# W5500_Module.net
KiCad netlist of a schematic drawn in Altium Designer
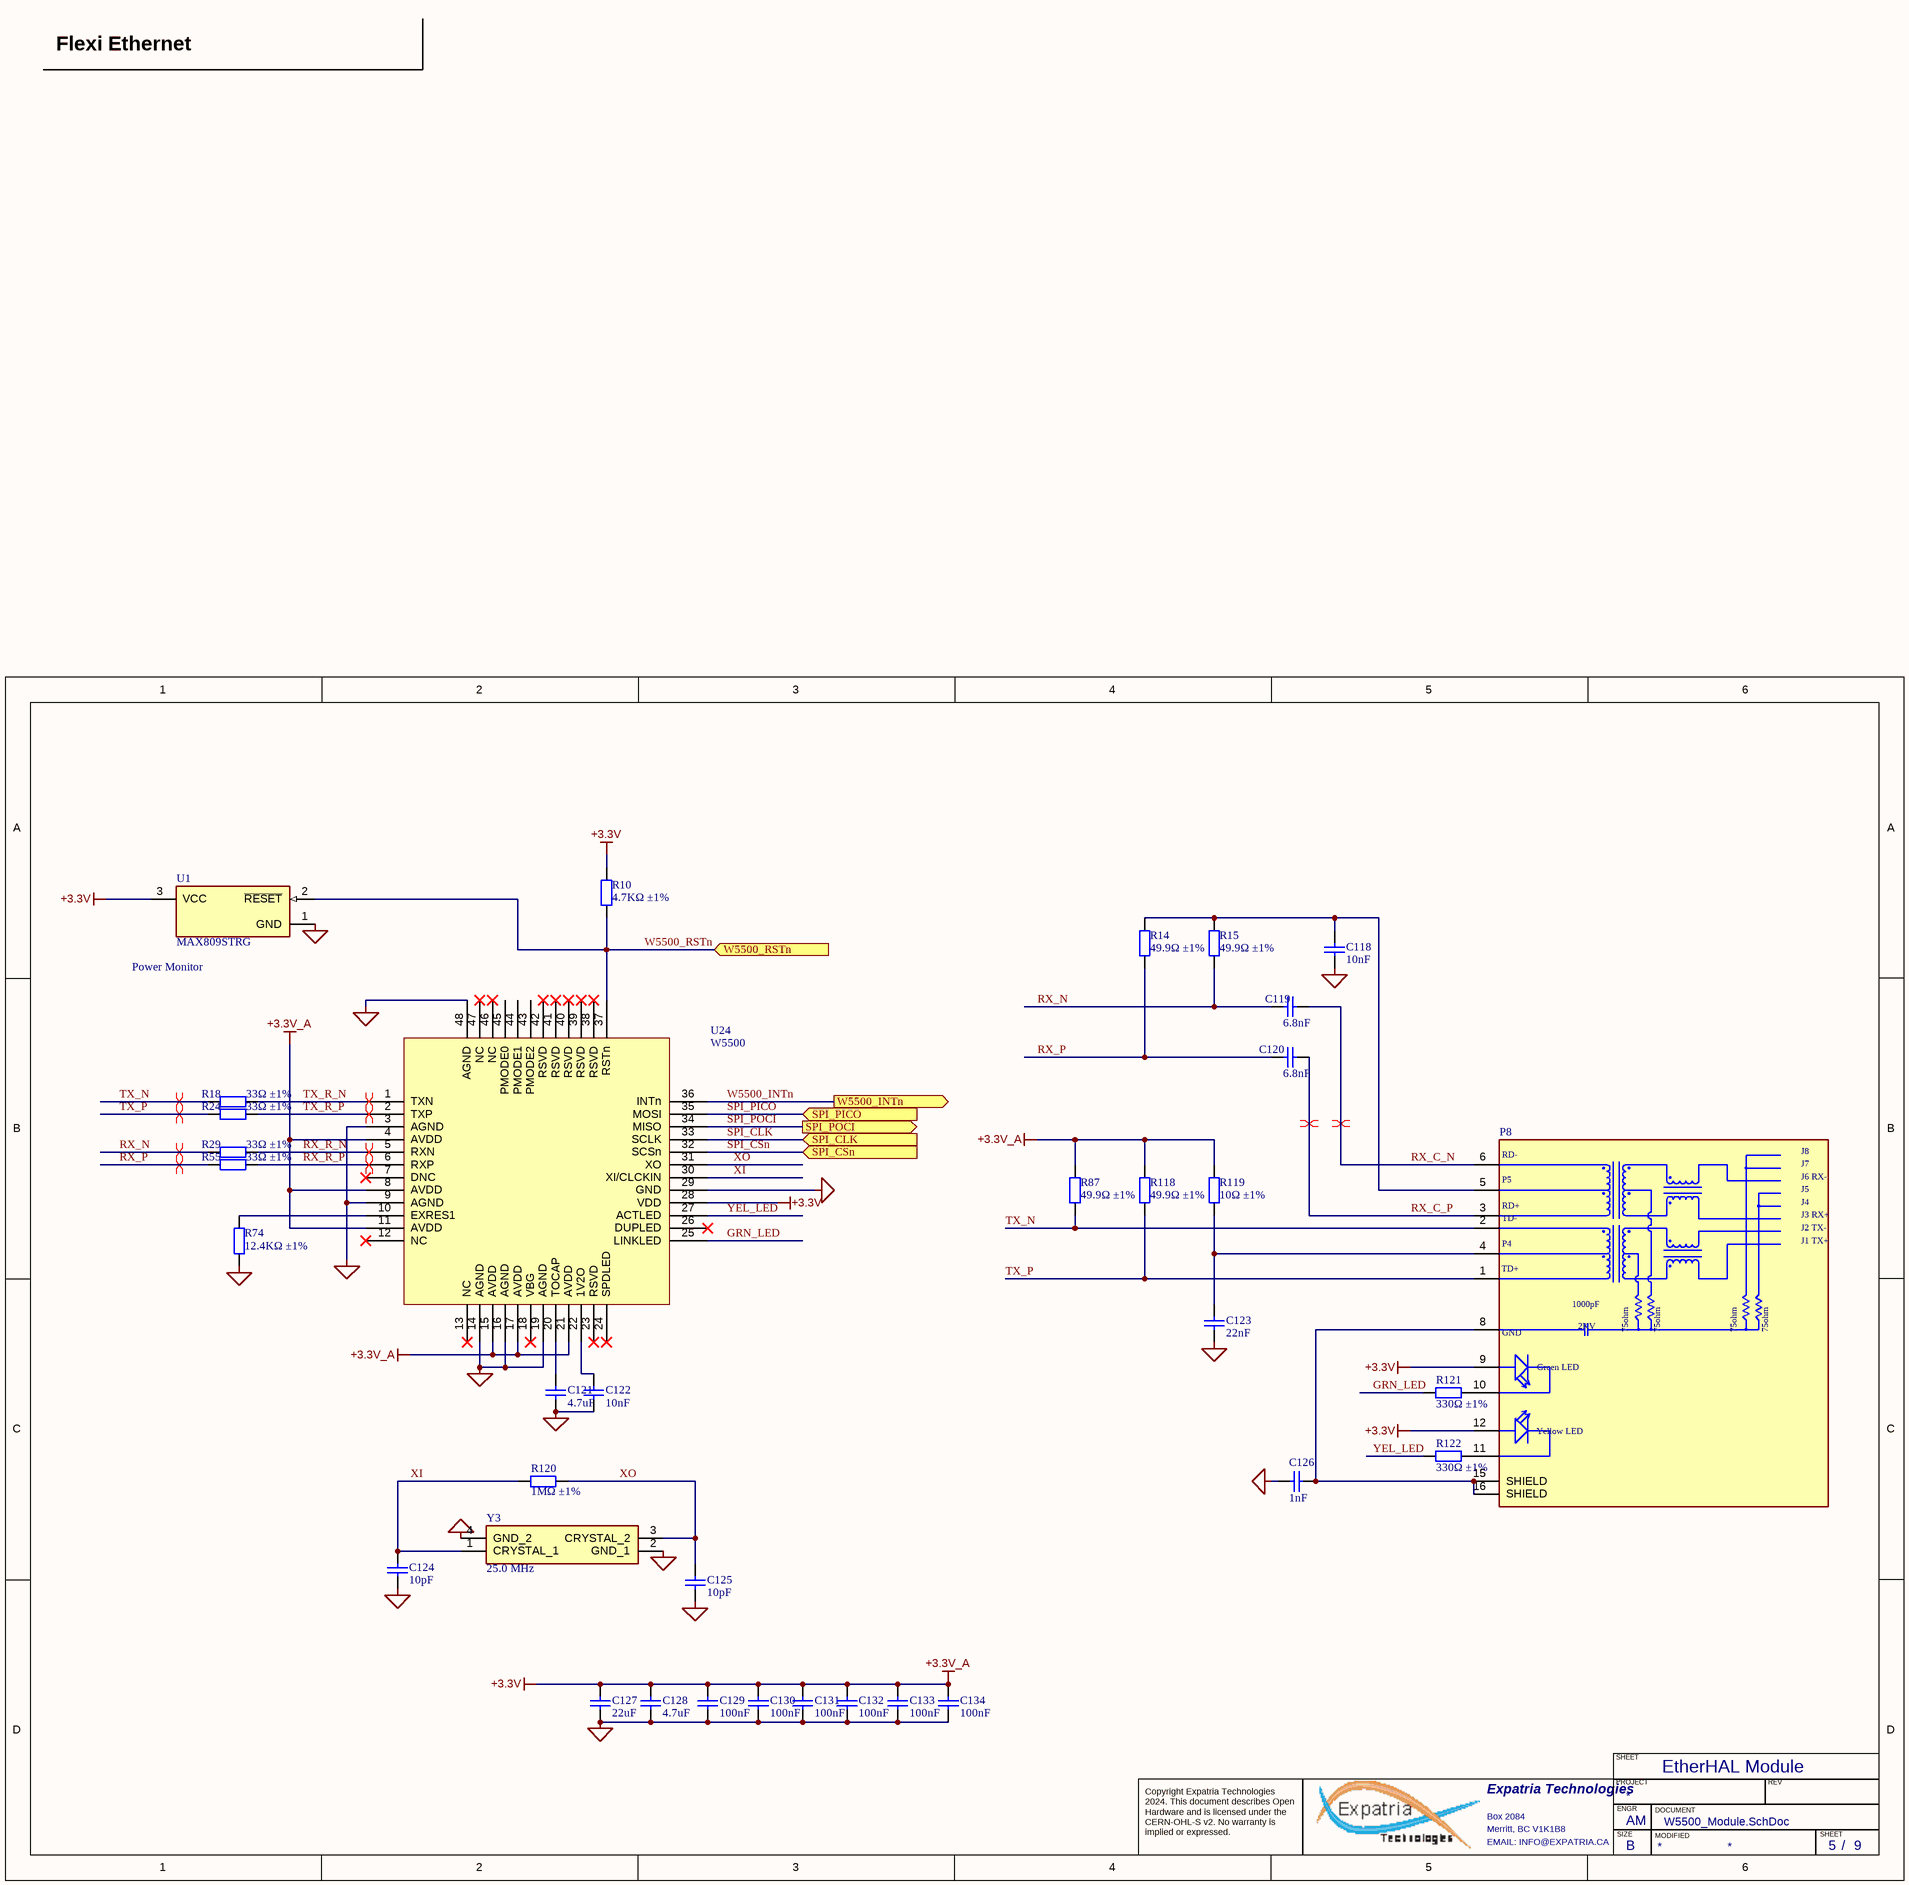
[diagram p0: W5500_Module.SchDoc]

(export (version "E")
  (design (tool "Eeschema 10.0.6"))
  (components
    (comp (ref "C118")
      (value "10nF")
      (footprint "0402_C")
      (description "Chip capacitors")
      (fields
        (field (name "MANUFACTURER") "Samsung Electro-Mechanics")
        (field (name "PARTNUMBER") "CL05B103KB5NNNC")
      )
      (libsource (lib "Cap") (part "0402 10nF (103) 10% 50V"))
    )
    (comp (ref "C119")
      (value "6.8nF")
      (footprint "0402_C")
      (description "Chip capacitors")
      (fields
        (field (name "MANUFACTURER") "Guangdong Fenghua Advanced Tech")
        (field (name "PARTNUMBER") "0402B682K500NT")
      )
      (libsource (lib "Cap") (part "0402 6.8nF (682) 10% 50V"))
    )
    (comp (ref "C120")
      (value "6.8nF")
      (footprint "0402_C")
      (description "Chip capacitors")
      (fields
        (field (name "MANUFACTURER") "Guangdong Fenghua Advanced Tech")
        (field (name "PARTNUMBER") "0402B682K500NT")
      )
      (libsource (lib "Cap") (part "0402 6.8nF (682) 10% 50V"))
    )
    (comp (ref "C121")
      (value "4.7uF")
      (footprint "0402_C")
      (description "Chip capacitor")
      (fields
        (field (name "MANUFACTURER") "Samsung Electro-Mechanics")
        (field (name "PARTNUMBER") "CL05A475MP5NRNC")
      )
      (libsource (lib "Cap") (part "0402 4.7uF (475) 20% 10V"))
    )
    (comp (ref "C122")
      (value "10nF")
      (footprint "0402_C")
      (description "Chip capacitors")
      (fields
        (field (name "MANUFACTURER") "Samsung Electro-Mechanics")
        (field (name "PARTNUMBER") "CL05B103KB5NNNC")
      )
      (libsource (lib "Cap") (part "0402 10nF (103) 10% 50V"))
    )
    (comp (ref "C123")
      (value "22nF")
      (footprint "0402_C")
      (description "Chip capacitors")
      (fields
        (field (name "MANUFACTURER") "Guangdong Fenghua Advanced Tech")
        (field (name "PARTNUMBER") "0402B223K500NT")
      )
      (libsource (lib "Cap") (part "0402 22nF (223) 10% 50V"))
    )
    (comp (ref "C124")
      (value "10pF")
      (footprint "0402_C")
      (description "Chip capacitors")
      (fields
        (field (name "MANUFACTURER") "Samsung Electro-Mechanics")
        (field (name "PARTNUMBER") "CL05C100JB5NNNC")
      )
      (libsource (lib "Cap") (part "0402 10pF (100) 5% 50V"))
    )
    (comp (ref "C125")
      (value "10pF")
      (footprint "0402_C")
      (description "Chip capacitors")
      (fields
        (field (name "MANUFACTURER") "Samsung Electro-Mechanics")
        (field (name "PARTNUMBER") "CL05C100JB5NNNC")
      )
      (libsource (lib "Cap") (part "0402 10pF (100) 5% 50V"))
    )
    (comp (ref "C126")
      (value "1nF")
      (footprint "1206_C")
      (description "Chip capacitors")
      (fields
        (field (name "MANUFACTURER") "Samsung Electro-Mechanics")
        (field (name "PARTNUMBER") "CL31B102KGFNNNE")
      )
      (libsource (lib "Cap") (part "1206 1nF (102) 10% 500V"))
    )
    (comp (ref "C127")
      (value "22uF")
      (footprint "0805_C")
      (description "Chip capacitors")
      (fields
        (field (name "MANUFACTURER") "Samsung Electro-Mechanics")
        (field (name "PARTNUMBER") "CL21A226MAQNNNE")
      )
      (libsource (lib "Cap") (part "0805 22uF (226) 20% 25V"))
    )
    (comp (ref "C128")
      (value "4.7uF")
      (footprint "0603_C")
      (description "Chip capacitors")
      (fields
        (field (name "MANUFACTURER") "Samsung Electro-Mechanics")
        (field (name "PARTNUMBER") "CL10A475KO8NNNC")
      )
      (libsource (lib "Cap") (part "0603 4.7uF (475) 10% 16V"))
    )
    (comp (ref "C129")
      (value "100nF")
      (footprint "0402_C")
      (description "Chip capacitors")
      (fields
        (field (name "MANUFACTURER") "Samsung Electro-Mechanics")
        (field (name "PARTNUMBER") "CL05B104KO5NNNC")
      )
      (libsource (lib "Cap") (part "0402 100nF (104) 10% 16V"))
    )
    (comp (ref "C130")
      (value "100nF")
      (footprint "0402_C")
      (description "Chip capacitors")
      (fields
        (field (name "MANUFACTURER") "Samsung Electro-Mechanics")
        (field (name "PARTNUMBER") "CL05B104KO5NNNC")
      )
      (libsource (lib "Cap") (part "0402 100nF (104) 10% 16V"))
    )
    (comp (ref "C131")
      (value "100nF")
      (footprint "0402_C")
      (description "Chip capacitors")
      (fields
        (field (name "MANUFACTURER") "Samsung Electro-Mechanics")
        (field (name "PARTNUMBER") "CL05B104KO5NNNC")
      )
      (libsource (lib "Cap") (part "0402 100nF (104) 10% 16V"))
    )
    (comp (ref "C132")
      (value "100nF")
      (footprint "0402_C")
      (description "Chip capacitors")
      (fields
        (field (name "MANUFACTURER") "Samsung Electro-Mechanics")
        (field (name "PARTNUMBER") "CL05B104KO5NNNC")
      )
      (libsource (lib "Cap") (part "0402 100nF (104) 10% 16V"))
    )
    (comp (ref "C133")
      (value "100nF")
      (footprint "0402_C")
      (description "Chip capacitors")
      (fields
        (field (name "MANUFACTURER") "Samsung Electro-Mechanics")
        (field (name "PARTNUMBER") "CL05B104KO5NNNC")
      )
      (libsource (lib "Cap") (part "0402 100nF (104) 10% 16V"))
    )
    (comp (ref "C134")
      (value "100nF")
      (footprint "0402_C")
      (description "Chip capacitors")
      (fields
        (field (name "MANUFACTURER") "Samsung Electro-Mechanics")
        (field (name "PARTNUMBER") "CL05B104KO5NNNC")
      )
      (libsource (lib "Cap") (part "0402 100nF (104) 10% 16V"))
    )
    (comp (ref "P8")
      (value "~")
      (footprint "HANRUN_HR911105A")
      (description "HR911105A Ethernet Interface Arduino Platform Evaluation Expansion Board")
      (fields (field (name "MP") "HR911105A") (field (name "MF") "DFRobot"))
      (libsource (lib "Universal_CNC_Breakout") (part "HR911105A"))
    )
    (comp (ref "R10")
      (value "4.7KΩ ±1%")
      (footprint "0402_R")
      (description "Chip resistor")
      (fields (field (name "MANUFACTURER") "Uniroyal Elec") (field (name "PARTNUMBER") "0402WGF4701TCE"))
      (libsource (lib "RES") (part "0402 4.7K (4701) 1%"))
    )
    (comp (ref "R14")
      (value "49.9Ω ±1%")
      (footprint "0402_R")
      (description "Chip resistor")
      (fields (field (name "MANUFACTURER") "Uniroyal Elec") (field (name "PARTNUMBER") "0402WGF499JTCE"))
      (libsource (lib "RES") (part "0402 49.9R (49R9) 1%"))
    )
    (comp (ref "R15")
      (value "49.9Ω ±1%")
      (footprint "0402_R")
      (description "Chip resistor")
      (fields (field (name "MANUFACTURER") "Uniroyal Elec") (field (name "PARTNUMBER") "0402WGF499JTCE"))
      (libsource (lib "RES") (part "0402 49.9R (49R9) 1%"))
    )
    (comp (ref "R18")
      (value "33Ω ±1%")
      (footprint "0402_R")
      (description "Chip resistor")
      (fields (field (name "MANUFACTURER") "Uniroyal Elec") (field (name "PARTNUMBER") "0402WGF330JTCE"))
      (libsource (lib "RES") (part "0402 33R (33R0) 1%"))
    )
    (comp (ref "R24")
      (value "33Ω ±1%")
      (footprint "0402_R")
      (description "Chip resistor")
      (fields (field (name "MANUFACTURER") "Uniroyal Elec") (field (name "PARTNUMBER") "0402WGF330JTCE"))
      (libsource (lib "RES") (part "0402 33R (33R0) 1%"))
    )
    (comp (ref "R29")
      (value "33Ω ±1%")
      (footprint "0402_R")
      (description "Chip resistor")
      (fields (field (name "MANUFACTURER") "Uniroyal Elec") (field (name "PARTNUMBER") "0402WGF330JTCE"))
      (libsource (lib "RES") (part "0402 33R (33R0) 1%"))
    )
    (comp (ref "R55")
      (value "33Ω ±1%")
      (footprint "0402_R")
      (description "Chip resistor")
      (fields (field (name "MANUFACTURER") "Uniroyal Elec") (field (name "PARTNUMBER") "0402WGF330JTCE"))
      (libsource (lib "RES") (part "0402 33R (33R0) 1%"))
    )
    (comp (ref "R74")
      (value "12.4KΩ ±1%")
      (footprint "0603_R")
      (description "Chip resistor")
      (fields (field (name "MANUFACTURER") "Uniroyal Elec") (field (name "PARTNUMBER") "0603WAF1242T5E"))
      (libsource (lib "RES") (part "0603 10K (1002) 1%"))
    )
    (comp (ref "R87")
      (value "49.9Ω ±1%")
      (footprint "0402_R")
      (description "Chip resistor")
      (fields (field (name "MANUFACTURER") "Uniroyal Elec") (field (name "PARTNUMBER") "0402WGF499JTCE"))
      (libsource (lib "RES") (part "0402 49.9R (49R9) 1%"))
    )
    (comp (ref "R118")
      (value "49.9Ω ±1%")
      (footprint "0402_R")
      (description "Chip resistor")
      (fields (field (name "MANUFACTURER") "Uniroyal Elec") (field (name "PARTNUMBER") "0402WGF499JTCE"))
      (libsource (lib "RES") (part "0402 49.9R (49R9) 1%"))
    )
    (comp (ref "R119")
      (value "10Ω ±1%")
      (footprint "0402_R")
      (description "Chip resistor")
      (fields (field (name "MANUFACTURER") "Uniroyal Elec") (field (name "PARTNUMBER") "0402WGF100JTCE"))
      (libsource (lib "RES") (part "0402 10R (10R0) 1%"))
    )
    (comp (ref "R120")
      (value "1MΩ ±1%")
      (footprint "0402_R")
      (description "Chip resistor")
      (fields (field (name "MANUFACTURER") "Uniroyal Elec") (field (name "PARTNUMBER") "0402WGF1004TCE"))
      (libsource (lib "RES") (part "0402 1M (1004) 1%"))
    )
    (comp (ref "R121")
      (value "330Ω ±1%")
      (footprint "0402_R")
      (description "Chip resistor")
      (fields (field (name "MANUFACTURER") "Uniroyal Elec") (field (name "PARTNUMBER") "0402WGF3300TCE"))
      (libsource (lib "RES") (part "0402 330R (3300) 1%"))
    )
    (comp (ref "R122")
      (value "330Ω ±1%")
      (footprint "0402_R")
      (description "Chip resistor")
      (fields (field (name "MANUFACTURER") "Uniroyal Elec") (field (name "PARTNUMBER") "0402WGF3300TCE"))
      (libsource (lib "RES") (part "0402 330R (3300) 1%"))
    )
    (comp (ref "U1")
      (value "MAX809STRG")
      (footprint "FP-318-08-MFG")
      (description "IC MPU SUPERVISORY 2.93V SOT23")
      (fields
        (field (name "OCTOPART") "https://octopart.com/max809strg-on+semiconductor-509853")
        (field (name "MANUFACTURER") "ON SEMICONDUCTOR")
      )
      (libsource (lib "Altium Content Vault") (part "10e2fe7115e7b167e7ed62dcbcd754e"))
    )
    (comp (ref "U24")
      (value "W5500")
      (footprint "LQFP-48_7x7x05P")
      (description "Ethernet Controllers 2.97V ~ 3.63V 10/100 Base-T/TX PHY SPI LQFP-48_7x7x05P Ethernet ICs ROHS")
      (libsource (lib "IC") (part "W5500_[C32843]"))
    )
    (comp (ref "Y3")
      (value "25.0 MHz")
      (footprint "YSX321SL")
      (description "Crystal or Oscillator")
      (fields (field (name "MANUFACTURER_PART_NUMBER") "X322525MSB4SI"))
      (libsource (lib "*") (part "YSX321SL"))
    )
  )
  (nets
    (net (code "1") (name "+3.3V") (class "Default")
      (node (ref "C127") (pin "2") (pinfunction "2_2") (pintype "passive"))
      (node (ref "C128") (pin "2") (pinfunction "2_2") (pintype "passive"))
      (node (ref "C129") (pin "2") (pinfunction "2_2") (pintype "passive"))
      (node (ref "C130") (pin "2") (pinfunction "2_2") (pintype "passive"))
      (node (ref "C131") (pin "2") (pinfunction "2_2") (pintype "passive"))
      (node (ref "C132") (pin "2") (pinfunction "2_2") (pintype "passive"))
      (node (ref "C133") (pin "2") (pinfunction "2_2") (pintype "passive"))
      (node (ref "C134") (pin "2") (pinfunction "2_2") (pintype "passive"))
      (node (ref "P8") (pin "12") (pinfunction "YA_12") (pintype "passive"))
      (node (ref "P8") (pin "9") (pinfunction "GA_9") (pintype "passive"))
      (node (ref "R10") (pin "1") (pinfunction "1_1") (pintype "passive"))
      (node (ref "R118") (pin "1") (pinfunction "1_1") (pintype "passive"))
      (node (ref "R119") (pin "1") (pinfunction "1_1") (pintype "passive"))
      (node (ref "R87") (pin "1") (pinfunction "1_1") (pintype "passive"))
      (node (ref "U1") (pin "3") (pinfunction "VCC_3") (pintype "power_in"))
      (node (ref "U24") (pin "11") (pinfunction "AVDD_11") (pintype "passive"))
      (node (ref "U24") (pin "15") (pinfunction "AVDD_15") (pintype "passive"))
      (node (ref "U24") (pin "17") (pinfunction "AVDD_17") (pintype "passive"))
      (node (ref "U24") (pin "21") (pinfunction "AVDD_21") (pintype "passive"))
      (node (ref "U24") (pin "28") (pinfunction "VDD_28") (pintype "passive"))
      (node (ref "U24") (pin "4") (pinfunction "AVDD_4") (pintype "passive"))
      (node (ref "U24") (pin "8") (pinfunction "AVDD_8") (pintype "passive"))
    )
    (net (code "2") (name "/GRN_LED") (class "Default")
      (node (ref "R121") (pin "1") (pinfunction "1_1") (pintype "passive"))
      (node (ref "U24") (pin "25") (pinfunction "LINKLED_25") (pintype "passive"))
    )
    (net (code "3") (name "/RX_C_N") (class "Default")
      (node (ref "C119") (pin "1") (pinfunction "1_1") (pintype "passive"))
      (node (ref "P8") (pin "6") (pinfunction "RD-_6") (pintype "passive"))
    )
    (net (code "4") (name "/RX_C_P") (class "Default")
      (node (ref "C120") (pin "1") (pinfunction "1_1") (pintype "passive"))
      (node (ref "P8") (pin "3") (pinfunction "RD+_3") (pintype "passive"))
    )
    (net (code "5") (name "/RX_N") (class "Default")
      (node (ref "C119") (pin "2") (pinfunction "2_2") (pintype "passive"))
      (node (ref "R15") (pin "2") (pinfunction "2_2") (pintype "passive"))
      (node (ref "R29") (pin "1") (pinfunction "1_1") (pintype "passive"))
    )
    (net (code "6") (name "/RX_P") (class "Default")
      (node (ref "C120") (pin "2") (pinfunction "2_2") (pintype "passive"))
      (node (ref "R14") (pin "2") (pinfunction "2_2") (pintype "passive"))
      (node (ref "R55") (pin "1") (pinfunction "1_1") (pintype "passive"))
    )
    (net (code "7") (name "/RX_R_N") (class "Default")
      (node (ref "R29") (pin "2") (pinfunction "2_2") (pintype "passive"))
      (node (ref "U24") (pin "5") (pinfunction "RXN_5") (pintype "passive"))
    )
    (net (code "8") (name "/RX_R_P") (class "Default")
      (node (ref "R55") (pin "2") (pinfunction "2_2") (pintype "passive"))
      (node (ref "U24") (pin "6") (pinfunction "RXP_6") (pintype "passive"))
    )
    (net (code "9") (name "/SPI_CLK") (class "Default")
      (node (ref "U24") (pin "33") (pinfunction "SCLK_33") (pintype "passive"))
    )
    (net (code "10") (name "/SPI_CSn") (class "Default")
      (node (ref "U24") (pin "32") (pinfunction "SCSn_32") (pintype "passive"))
    )
    (net (code "11") (name "/SPI_PICO") (class "Default")
      (node (ref "U24") (pin "35") (pinfunction "MOSI_35") (pintype "passive"))
    )
    (net (code "12") (name "/SPI_POCI") (class "Default")
      (node (ref "U24") (pin "34") (pinfunction "MISO_34") (pintype "passive"))
    )
    (net (code "13") (name "/TX_N") (class "Default")
      (node (ref "P8") (pin "2") (pinfunction "TD-_2") (pintype "passive"))
      (node (ref "R18") (pin "1") (pinfunction "1_1") (pintype "passive"))
      (node (ref "R87") (pin "2") (pinfunction "2_2") (pintype "passive"))
    )
    (net (code "14") (name "/TX_P") (class "Default")
      (node (ref "P8") (pin "1") (pinfunction "TD+_1") (pintype "passive"))
      (node (ref "R118") (pin "2") (pinfunction "2_2") (pintype "passive"))
      (node (ref "R24") (pin "1") (pinfunction "1_1") (pintype "passive"))
    )
    (net (code "15") (name "/TX_R_N") (class "Default")
      (node (ref "R18") (pin "2") (pinfunction "2_2") (pintype "passive"))
      (node (ref "U24") (pin "1") (pinfunction "TXN_1") (pintype "passive"))
    )
    (net (code "16") (name "/TX_R_P") (class "Default")
      (node (ref "R24") (pin "2") (pinfunction "2_2") (pintype "passive"))
      (node (ref "U24") (pin "2") (pinfunction "TXP_2") (pintype "passive"))
    )
    (net (code "17") (name "/W5500_INTn") (class "Default")
      (node (ref "U24") (pin "36") (pinfunction "INTn_36") (pintype "passive"))
    )
    (net (code "18") (name "/W5500_RSTn") (class "Default")
      (node (ref "R10") (pin "2") (pinfunction "2_2") (pintype "passive"))
      (node (ref "U1") (pin "2") (pinfunction "~{RESET}_2") (pintype "input"))
      (node (ref "U24") (pin "37") (pinfunction "RSTn_37") (pintype "passive"))
    )
    (net (code "19") (name "/XI") (class "Default")
      (node (ref "C124") (pin "2") (pinfunction "2_2") (pintype "passive"))
      (node (ref "R120") (pin "1") (pinfunction "1_1") (pintype "passive"))
      (node (ref "U24") (pin "30") (pinfunction "XI/CLCKIN_30") (pintype "passive"))
      (node (ref "Y3") (pin "1") (pinfunction "CRYSTAL_1_1") (pintype "passive"))
    )
    (net (code "20") (name "/XO") (class "Default")
      (node (ref "C125") (pin "2") (pinfunction "2_2") (pintype "passive"))
      (node (ref "R120") (pin "2") (pinfunction "2_2") (pintype "passive"))
      (node (ref "U24") (pin "31") (pinfunction "XO_31") (pintype "passive"))
      (node (ref "Y3") (pin "3") (pinfunction "CRYSTAL_2_3") (pintype "passive"))
    )
    (net (code "21") (name "/YEL_LED") (class "Default")
      (node (ref "R122") (pin "1") (pinfunction "1_1") (pintype "passive"))
      (node (ref "U24") (pin "27") (pinfunction "ACTLED_27") (pintype "passive"))
    )
    (net (code "22") (name "MCU_GND") (class "Default")
      (node (ref "C118") (pin "1") (pinfunction "1_1") (pintype "passive"))
      (node (ref "C121") (pin "1") (pinfunction "1_1") (pintype "passive"))
      (node (ref "C122") (pin "1") (pinfunction "1_1") (pintype "passive"))
      (node (ref "C123") (pin "1") (pinfunction "1_1") (pintype "passive"))
      (node (ref "C124") (pin "1") (pinfunction "1_1") (pintype "passive"))
      (node (ref "C125") (pin "1") (pinfunction "1_1") (pintype "passive"))
      (node (ref "C126") (pin "1") (pinfunction "1_1") (pintype "passive"))
      (node (ref "C127") (pin "1") (pinfunction "1_1") (pintype "passive"))
      (node (ref "C128") (pin "1") (pinfunction "1_1") (pintype "passive"))
      (node (ref "C129") (pin "1") (pinfunction "1_1") (pintype "passive"))
      (node (ref "C130") (pin "1") (pinfunction "1_1") (pintype "passive"))
      (node (ref "C131") (pin "1") (pinfunction "1_1") (pintype "passive"))
      (node (ref "C132") (pin "1") (pinfunction "1_1") (pintype "passive"))
      (node (ref "C133") (pin "1") (pinfunction "1_1") (pintype "passive"))
      (node (ref "C134") (pin "1") (pinfunction "1_1") (pintype "passive"))
      (node (ref "R74") (pin "1") (pinfunction "1_1") (pintype "passive"))
      (node (ref "U1") (pin "1") (pinfunction "GND_1") (pintype "power_in"))
      (node (ref "U24") (pin "14") (pinfunction "AGND_14") (pintype "passive"))
      (node (ref "U24") (pin "16") (pinfunction "AGND_16") (pintype "passive"))
      (node (ref "U24") (pin "19") (pinfunction "AGND_19") (pintype "passive"))
      (node (ref "U24") (pin "29") (pinfunction "GND_29") (pintype "passive"))
      (node (ref "U24") (pin "3") (pinfunction "AGND_3") (pintype "passive"))
      (node (ref "U24") (pin "48") (pinfunction "AGND_48") (pintype "passive"))
      (node (ref "U24") (pin "9") (pinfunction "AGND_9") (pintype "passive"))
      (node (ref "Y3") (pin "2") (pinfunction "GND_1_2") (pintype "passive"))
      (node (ref "Y3") (pin "4") (pinfunction "GND_2_4") (pintype "passive"))
    )
    (net (code "23") (name "Net-(P8-GC)") (class "Default")
      (node (ref "P8") (pin "10") (pinfunction "GC_10") (pintype "passive"))
      (node (ref "R121") (pin "2") (pinfunction "2_2") (pintype "passive"))
    )
    (net (code "24") (name "Net-(P8-GND)") (class "Default")
      (node (ref "C126") (pin "2") (pinfunction "2_2") (pintype "passive"))
      (node (ref "P8") (pin "15") (pinfunction "SHIELD_15") (pintype "passive"))
      (node (ref "P8") (pin "16") (pinfunction "SHIELD_16") (pintype "passive"))
      (node (ref "P8") (pin "8") (pinfunction "GND_8") (pintype "power_in"))
    )
    (net (code "25") (name "Net-(P8-P4)") (class "Default")
      (node (ref "C123") (pin "2") (pinfunction "2_2") (pintype "passive"))
      (node (ref "P8") (pin "4") (pinfunction "P4_4") (pintype "passive"))
      (node (ref "R119") (pin "2") (pinfunction "2_2") (pintype "passive"))
    )
    (net (code "26") (name "Net-(P8-P5)") (class "Default")
      (node (ref "C118") (pin "2") (pinfunction "2_2") (pintype "passive"))
      (node (ref "P8") (pin "5") (pinfunction "P5_5") (pintype "passive"))
      (node (ref "R14") (pin "1") (pinfunction "1_1") (pintype "passive"))
      (node (ref "R15") (pin "1") (pinfunction "1_1") (pintype "passive"))
    )
    (net (code "27") (name "Net-(P8-YC)") (class "Default")
      (node (ref "P8") (pin "11") (pinfunction "YC_11") (pintype "passive"))
      (node (ref "R122") (pin "2") (pinfunction "2_2") (pintype "passive"))
    )
    (net (code "28") (name "Net-(U24-1V2O)") (class "Default")
      (node (ref "C122") (pin "2") (pinfunction "2_2") (pintype "passive"))
      (node (ref "U24") (pin "22") (pinfunction "1V2O_22") (pintype "passive"))
    )
    (net (code "29") (name "Net-(U24-EXRES1)") (class "Default")
      (node (ref "R74") (pin "2") (pinfunction "2_2") (pintype "passive"))
      (node (ref "U24") (pin "10") (pinfunction "EXRES1_10") (pintype "passive"))
    )
    (net (code "30") (name "Net-(U24-TOCAP)") (class "Default")
      (node (ref "C121") (pin "2") (pinfunction "2_2") (pintype "passive"))
      (node (ref "U24") (pin "20") (pinfunction "TOCAP_20") (pintype "passive"))
    )
    (net (code "31") (name "unconnected-(U24-DNC-Pad7)") (class "Default")
      (node (ref "U24") (pin "7") (pinfunction "DNC_7") (pintype "passive+no_connect"))
    )
    (net (code "32") (name "unconnected-(U24-DUPLED-Pad26)") (class "Default")
      (node (ref "U24") (pin "26") (pinfunction "DUPLED_26") (pintype "passive+no_connect"))
    )
    (net (code "33") (name "unconnected-(U24-NC-Pad12)") (class "Default")
      (node (ref "U24") (pin "12") (pinfunction "NC_12") (pintype "passive+no_connect"))
    )
    (net (code "34") (name "unconnected-(U24-NC-Pad13)") (class "Default")
      (node (ref "U24") (pin "13") (pinfunction "NC_13") (pintype "passive+no_connect"))
    )
    (net (code "35") (name "unconnected-(U24-NC-Pad46)") (class "Default")
      (node (ref "U24") (pin "46") (pinfunction "NC_46") (pintype "passive+no_connect"))
    )
    (net (code "36") (name "unconnected-(U24-NC-Pad47)") (class "Default")
      (node (ref "U24") (pin "47") (pinfunction "NC_47") (pintype "passive+no_connect"))
    )
    (net (code "37") (name "unconnected-(U24-PMODE0-Pad45)") (class "Default")
      (node (ref "U24") (pin "45") (pinfunction "PMODE0_45") (pintype "passive"))
    )
    (net (code "38") (name "unconnected-(U24-PMODE1-Pad44)") (class "Default")
      (node (ref "U24") (pin "44") (pinfunction "PMODE1_44") (pintype "passive"))
    )
    (net (code "39") (name "unconnected-(U24-PMODE2-Pad43)") (class "Default")
      (node (ref "U24") (pin "43") (pinfunction "PMODE2_43") (pintype "passive"))
    )
    (net (code "40") (name "unconnected-(U24-RSVD-Pad23)") (class "Default")
      (node (ref "U24") (pin "23") (pinfunction "RSVD_23") (pintype "passive+no_connect"))
    )
    (net (code "41") (name "unconnected-(U24-RSVD-Pad38)") (class "Default")
      (node (ref "U24") (pin "38") (pinfunction "RSVD_38") (pintype "passive+no_connect"))
    )
    (net (code "42") (name "unconnected-(U24-RSVD-Pad39)") (class "Default")
      (node (ref "U24") (pin "39") (pinfunction "RSVD_39") (pintype "passive+no_connect"))
    )
    (net (code "43") (name "unconnected-(U24-RSVD-Pad40)") (class "Default")
      (node (ref "U24") (pin "40") (pinfunction "RSVD_40") (pintype "passive+no_connect"))
    )
    (net (code "44") (name "unconnected-(U24-RSVD-Pad41)") (class "Default")
      (node (ref "U24") (pin "41") (pinfunction "RSVD_41") (pintype "passive+no_connect"))
    )
    (net (code "45") (name "unconnected-(U24-RSVD-Pad42)") (class "Default")
      (node (ref "U24") (pin "42") (pinfunction "RSVD_42") (pintype "passive+no_connect"))
    )
    (net (code "46") (name "unconnected-(U24-SPDLED-Pad24)") (class "Default")
      (node (ref "U24") (pin "24") (pinfunction "SPDLED_24") (pintype "passive+no_connect"))
    )
    (net (code "47") (name "unconnected-(U24-VBG-Pad18)") (class "Default")
      (node (ref "U24") (pin "18") (pinfunction "VBG_18") (pintype "passive+no_connect"))
    )
  )
)
